# CNT_1_0.net
KiCad netlist of a schematic drawn in EAGLE
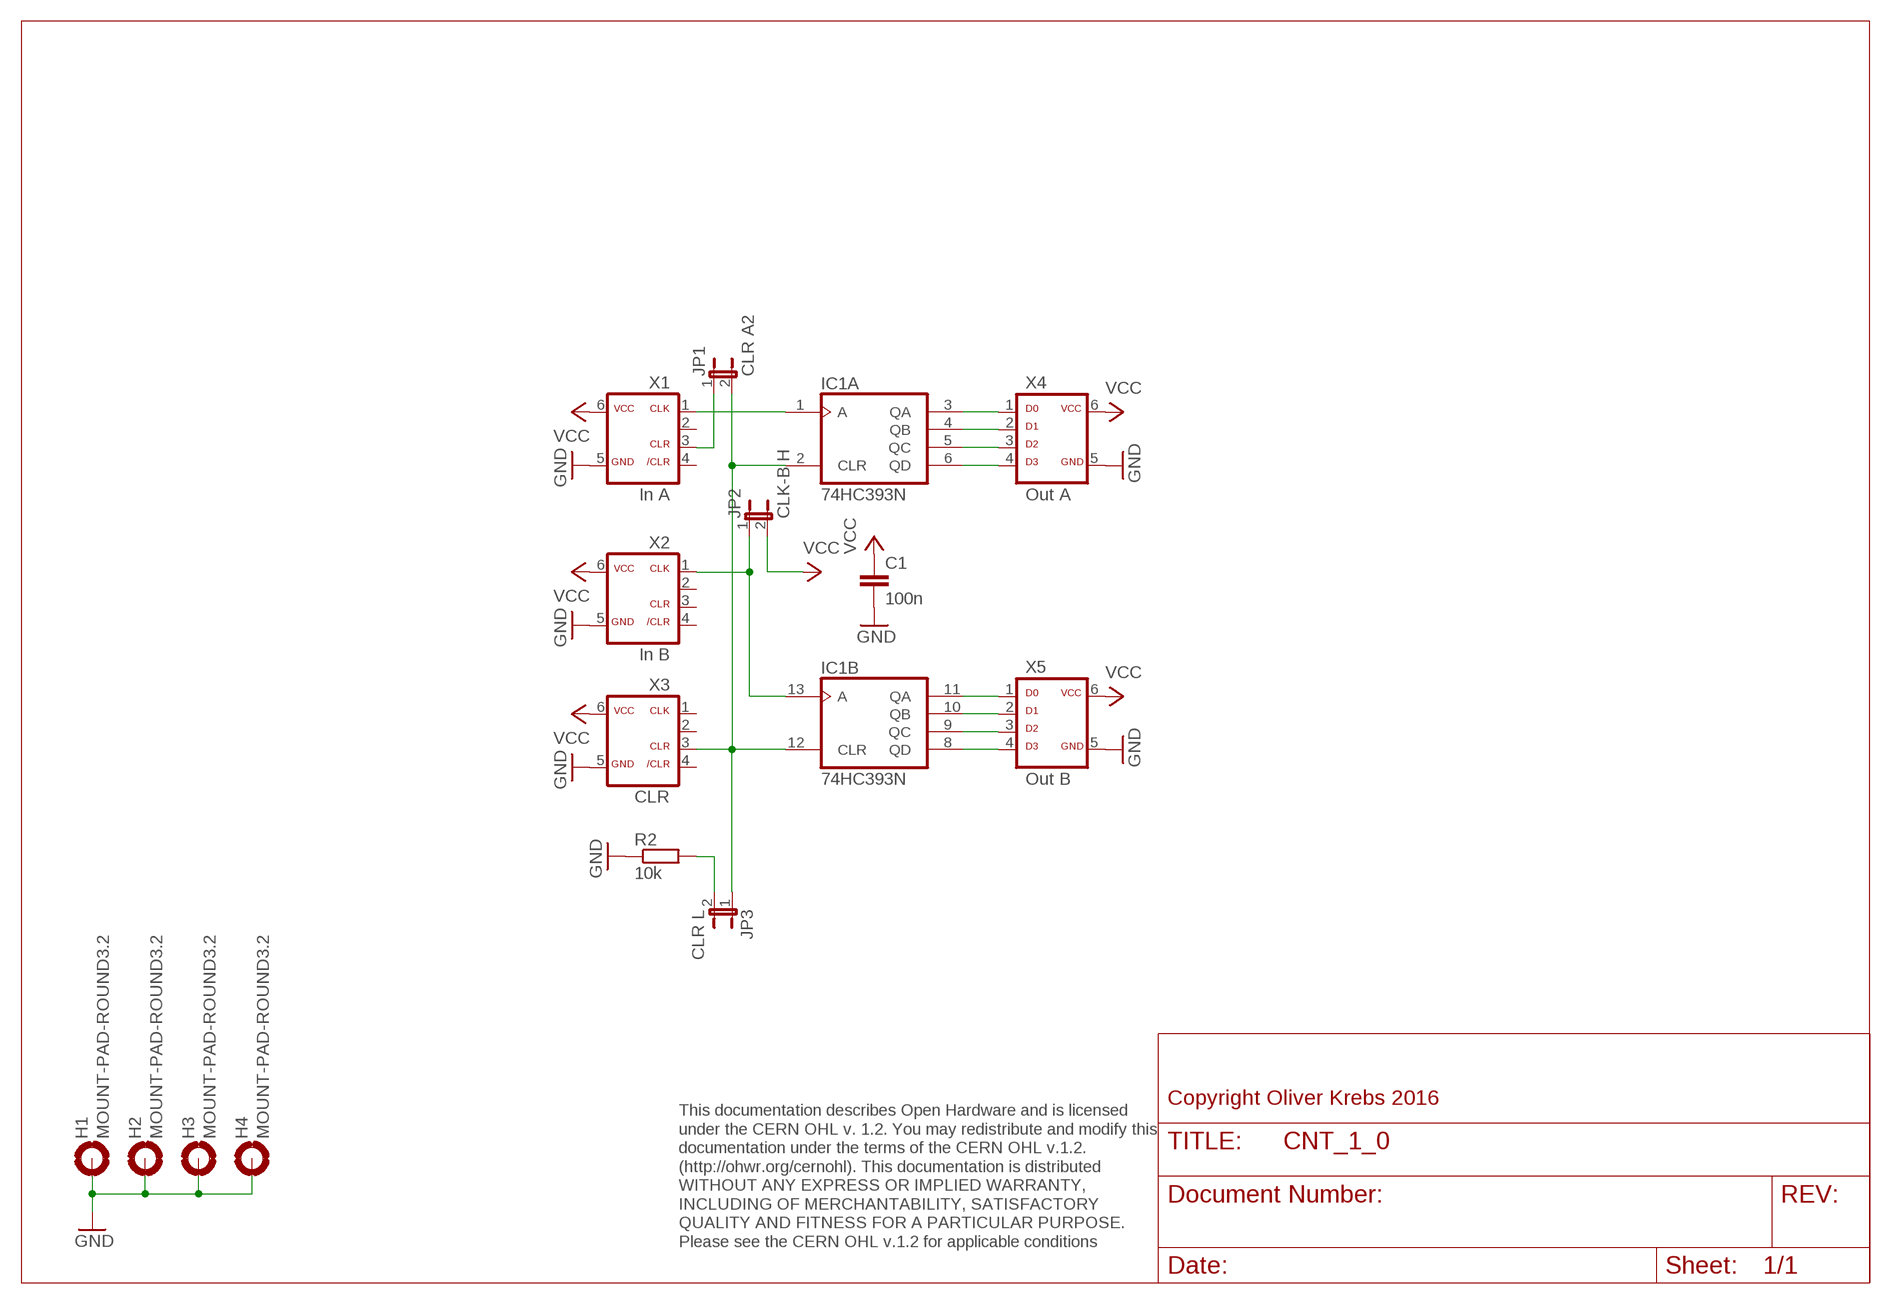
[diagram p0: schematic, sheet 1]

(export (version "E")
  (design (tool "Eeschema 10.0.6"))
  (components
    (comp (ref "C1")
      (value "100n")
      (footprint "eagle-import:C050-025X075")
      (libsource (lib "eagle-import") (part "C-EU050-025X075"))
    )
    (comp (ref "H1")
      (value "MOUNT-PAD-ROUND3.2")
      (footprint "eagle-import:3,2-PAD")
      (libsource (lib "eagle-import") (part "MOUNT-PAD-ROUND3.2"))
    )
    (comp (ref "H2")
      (value "MOUNT-PAD-ROUND3.2")
      (footprint "eagle-import:3,2-PAD")
      (libsource (lib "eagle-import") (part "MOUNT-PAD-ROUND3.2"))
    )
    (comp (ref "H3")
      (value "MOUNT-PAD-ROUND3.2")
      (footprint "eagle-import:3,2-PAD")
      (libsource (lib "eagle-import") (part "MOUNT-PAD-ROUND3.2"))
    )
    (comp (ref "H4")
      (value "MOUNT-PAD-ROUND3.2")
      (footprint "eagle-import:3,2-PAD")
      (libsource (lib "eagle-import") (part "MOUNT-PAD-ROUND3.2"))
    )
    (comp (ref "IC1")
      (value "74HC393N")
      (footprint "eagle-import:DIL14")
      (libsource (lib "eagle-import") (part "74393NHC"))
    )
    (comp (ref "JP1")
      (value "CLR A2")
      (footprint "eagle-import:JP1")
      (libsource (lib "eagle-import") (part "JP1E"))
    )
    (comp (ref "JP2")
      (value "CLK-B H")
      (footprint "eagle-import:JP1")
      (libsource (lib "eagle-import") (part "JP1E"))
    )
    (comp (ref "JP3")
      (value "CLR L")
      (footprint "eagle-import:JP1")
      (libsource (lib "eagle-import") (part "JP1E"))
    )
    (comp (ref "R2")
      (value "10k")
      (footprint "eagle-import:0207_10")
      (libsource (lib "eagle-import") (part "R-EU_0207/10"))
    )
    (comp (ref "X1")
      (value "In A")
      (footprint "eagle-import:ML-6")
      (libsource (lib "eagle-import") (part "ML6C"))
    )
    (comp (ref "X2")
      (value "In B")
      (footprint "eagle-import:ML-6")
      (libsource (lib "eagle-import") (part "ML6C"))
    )
    (comp (ref "X3")
      (value "CLR")
      (footprint "eagle-import:ML-6")
      (libsource (lib "eagle-import") (part "ML6C"))
    )
    (comp (ref "X4")
      (value "Out A")
      (footprint "eagle-import:ML-6")
      (libsource (lib "eagle-import") (part "ML6D"))
    )
    (comp (ref "X5")
      (value "Out B")
      (footprint "eagle-import:ML-6")
      (libsource (lib "eagle-import") (part "ML6D"))
    )
  )
  (nets
    (net (code "1") (name "GND") (class "Default")
      (node (ref "C1") (pin "2") (pinfunction "2_2") (pintype "passive"))
      (node (ref "H1") (pin "B3,2") (pinfunction "MOUNT_B3,2") (pintype "passive"))
      (node (ref "H2") (pin "B3,2") (pinfunction "MOUNT_B3,2") (pintype "passive"))
      (node (ref "H3") (pin "B3,2") (pinfunction "MOUNT_B3,2") (pintype "passive"))
      (node (ref "H4") (pin "B3,2") (pinfunction "MOUNT_B3,2") (pintype "passive"))
      (node (ref "R2") (pin "1") (pinfunction "1_1") (pintype "passive"))
      (node (ref "X1") (pin "5") (pinfunction "5_5") (pintype "passive"))
      (node (ref "X2") (pin "5") (pinfunction "5_5") (pintype "passive"))
      (node (ref "X3") (pin "5") (pinfunction "5_5") (pintype "passive"))
      (node (ref "X4") (pin "5") (pinfunction "5_5") (pintype "passive"))
      (node (ref "X5") (pin "5") (pinfunction "5_5") (pintype "passive"))
    )
    (net (code "2") (name "Net-(IC1A-A)") (class "Default")
      (node (ref "IC1") (pin "1") (pinfunction "A_1") (pintype "input"))
      (node (ref "X1") (pin "1") (pinfunction "1_1") (pintype "passive"))
    )
    (net (code "3") (name "Net-(IC1A-CLR)") (class "Default")
      (node (ref "IC1") (pin "12") (pinfunction "CLR_12") (pintype "input"))
      (node (ref "IC1") (pin "2") (pinfunction "CLR_2") (pintype "input"))
      (node (ref "JP1") (pin "2") (pinfunction "2_2") (pintype "passive"))
      (node (ref "JP3") (pin "1") (pinfunction "1_1") (pintype "passive"))
      (node (ref "X3") (pin "3") (pinfunction "3_3") (pintype "passive"))
    )
    (net (code "4") (name "Net-(IC1A-QA)") (class "Default")
      (node (ref "IC1") (pin "3") (pinfunction "QA_3") (pintype "output"))
      (node (ref "X4") (pin "1") (pinfunction "1_1") (pintype "passive"))
    )
    (net (code "5") (name "Net-(IC1A-QB)") (class "Default")
      (node (ref "IC1") (pin "4") (pinfunction "QB_4") (pintype "output"))
      (node (ref "X4") (pin "2") (pinfunction "2_2") (pintype "passive"))
    )
    (net (code "6") (name "Net-(IC1A-QC)") (class "Default")
      (node (ref "IC1") (pin "5") (pinfunction "QC_5") (pintype "output"))
      (node (ref "X4") (pin "3") (pinfunction "3_3") (pintype "passive"))
    )
    (net (code "7") (name "Net-(IC1A-QD)") (class "Default")
      (node (ref "IC1") (pin "6") (pinfunction "QD_6") (pintype "output"))
      (node (ref "X4") (pin "4") (pinfunction "4_4") (pintype "passive"))
    )
    (net (code "8") (name "Net-(IC1B-A)") (class "Default")
      (node (ref "IC1") (pin "13") (pinfunction "A_13") (pintype "input"))
      (node (ref "JP2") (pin "1") (pinfunction "1_1") (pintype "passive"))
      (node (ref "X2") (pin "1") (pinfunction "1_1") (pintype "passive"))
    )
    (net (code "9") (name "Net-(IC1B-QA)") (class "Default")
      (node (ref "IC1") (pin "11") (pinfunction "QA_11") (pintype "output"))
      (node (ref "X5") (pin "1") (pinfunction "1_1") (pintype "passive"))
    )
    (net (code "10") (name "Net-(IC1B-QB)") (class "Default")
      (node (ref "IC1") (pin "10") (pinfunction "QB_10") (pintype "output"))
      (node (ref "X5") (pin "2") (pinfunction "2_2") (pintype "passive"))
    )
    (net (code "11") (name "Net-(IC1B-QC)") (class "Default")
      (node (ref "IC1") (pin "9") (pinfunction "QC_9") (pintype "output"))
      (node (ref "X5") (pin "3") (pinfunction "3_3") (pintype "passive"))
    )
    (net (code "12") (name "Net-(IC1B-QD)") (class "Default")
      (node (ref "IC1") (pin "8") (pinfunction "QD_8") (pintype "output"))
      (node (ref "X5") (pin "4") (pinfunction "4_4") (pintype "passive"))
    )
    (net (code "13") (name "Net-(JP1-Pad1)") (class "Default")
      (node (ref "JP1") (pin "1") (pinfunction "1_1") (pintype "passive"))
      (node (ref "X1") (pin "3") (pinfunction "3_3") (pintype "passive"))
    )
    (net (code "14") (name "Net-(JP3-Pad2)") (class "Default")
      (node (ref "JP3") (pin "2") (pinfunction "2_2") (pintype "passive"))
      (node (ref "R2") (pin "2") (pinfunction "2_2") (pintype "passive"))
    )
    (net (code "15") (name "VCC") (class "Default")
      (node (ref "C1") (pin "1") (pinfunction "1_1") (pintype "passive"))
      (node (ref "JP2") (pin "2") (pinfunction "2_2") (pintype "passive"))
      (node (ref "X1") (pin "6") (pinfunction "6_6") (pintype "passive"))
      (node (ref "X2") (pin "6") (pinfunction "6_6") (pintype "passive"))
      (node (ref "X3") (pin "6") (pinfunction "6_6") (pintype "passive"))
      (node (ref "X4") (pin "6") (pinfunction "6_6") (pintype "passive"))
      (node (ref "X5") (pin "6") (pinfunction "6_6") (pintype "passive"))
    )
    (net (code "16") (name "unconnected-(X1-Pad2)") (class "Default")
      (node (ref "X1") (pin "2") (pinfunction "2_2") (pintype "passive"))
    )
    (net (code "17") (name "unconnected-(X1-Pad4)") (class "Default")
      (node (ref "X1") (pin "4") (pinfunction "4_4") (pintype "passive"))
    )
    (net (code "18") (name "unconnected-(X2-Pad2)") (class "Default")
      (node (ref "X2") (pin "2") (pinfunction "2_2") (pintype "passive"))
    )
    (net (code "19") (name "unconnected-(X2-Pad3)") (class "Default")
      (node (ref "X2") (pin "3") (pinfunction "3_3") (pintype "passive"))
    )
    (net (code "20") (name "unconnected-(X2-Pad4)") (class "Default")
      (node (ref "X2") (pin "4") (pinfunction "4_4") (pintype "passive"))
    )
    (net (code "21") (name "unconnected-(X3-Pad1)") (class "Default")
      (node (ref "X3") (pin "1") (pinfunction "1_1") (pintype "passive"))
    )
    (net (code "22") (name "unconnected-(X3-Pad2)") (class "Default")
      (node (ref "X3") (pin "2") (pinfunction "2_2") (pintype "passive"))
    )
    (net (code "23") (name "unconnected-(X3-Pad4)") (class "Default")
      (node (ref "X3") (pin "4") (pinfunction "4_4") (pintype "passive"))
    )
  )
)
